# u2x.net
KiCad netlist of a schematic drawn in EAGLE
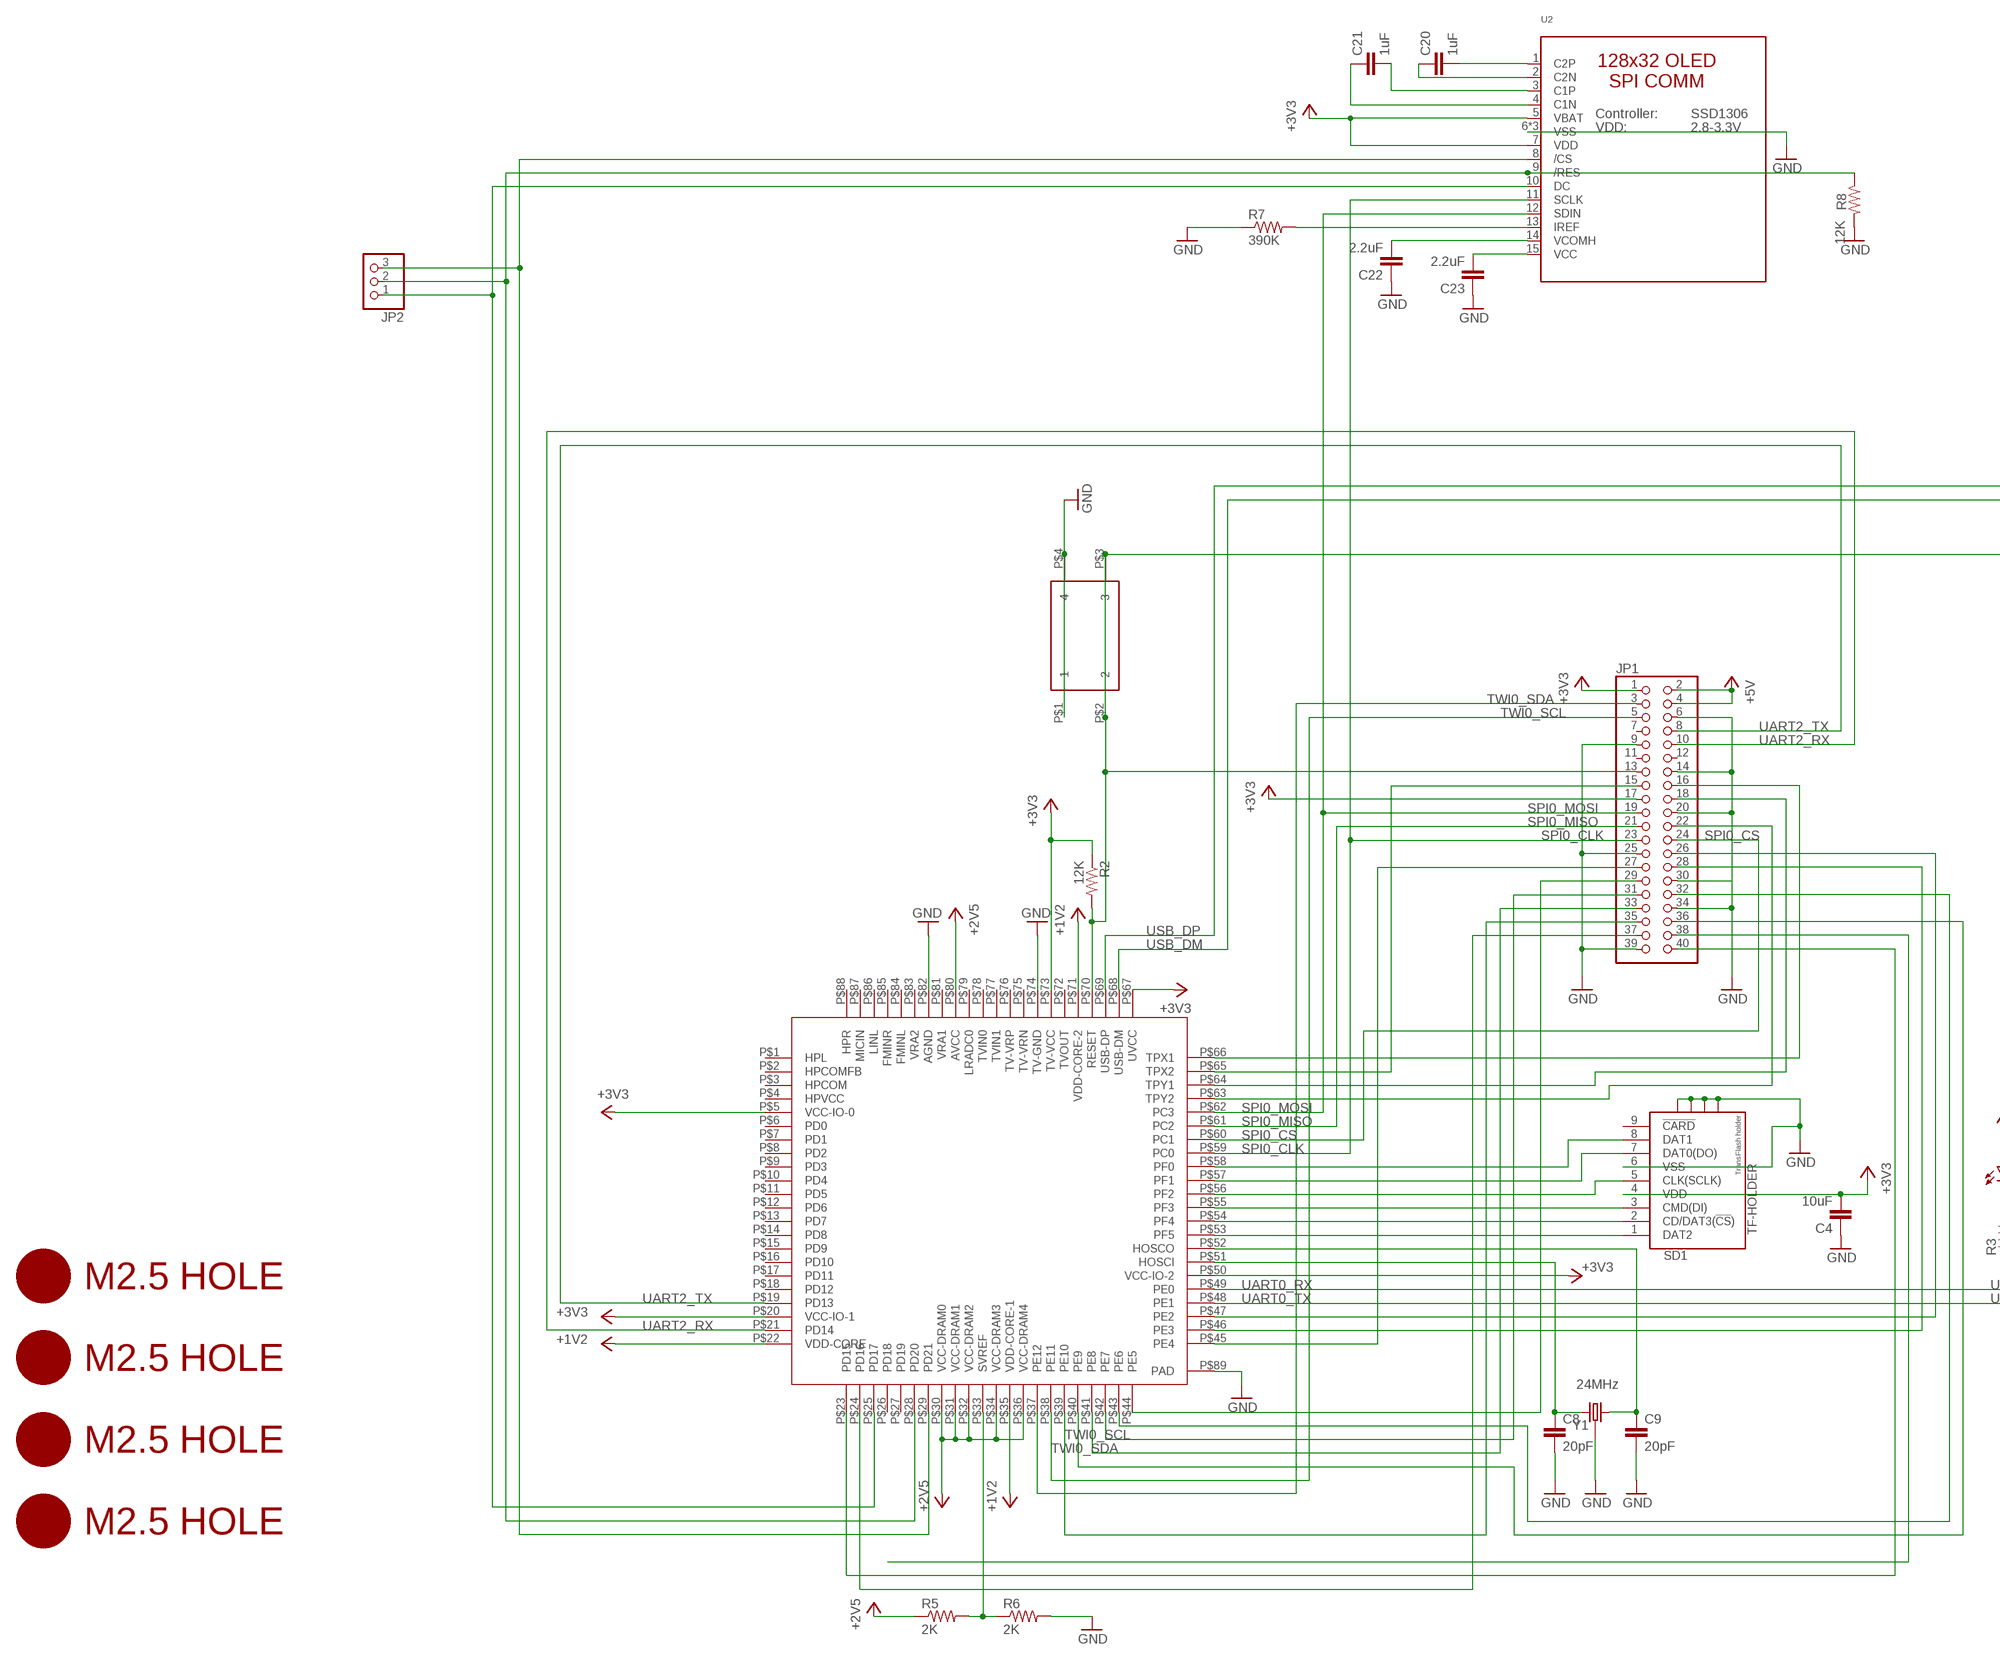
[diagram p0: schematic, sheet 1, part 1 of 2]
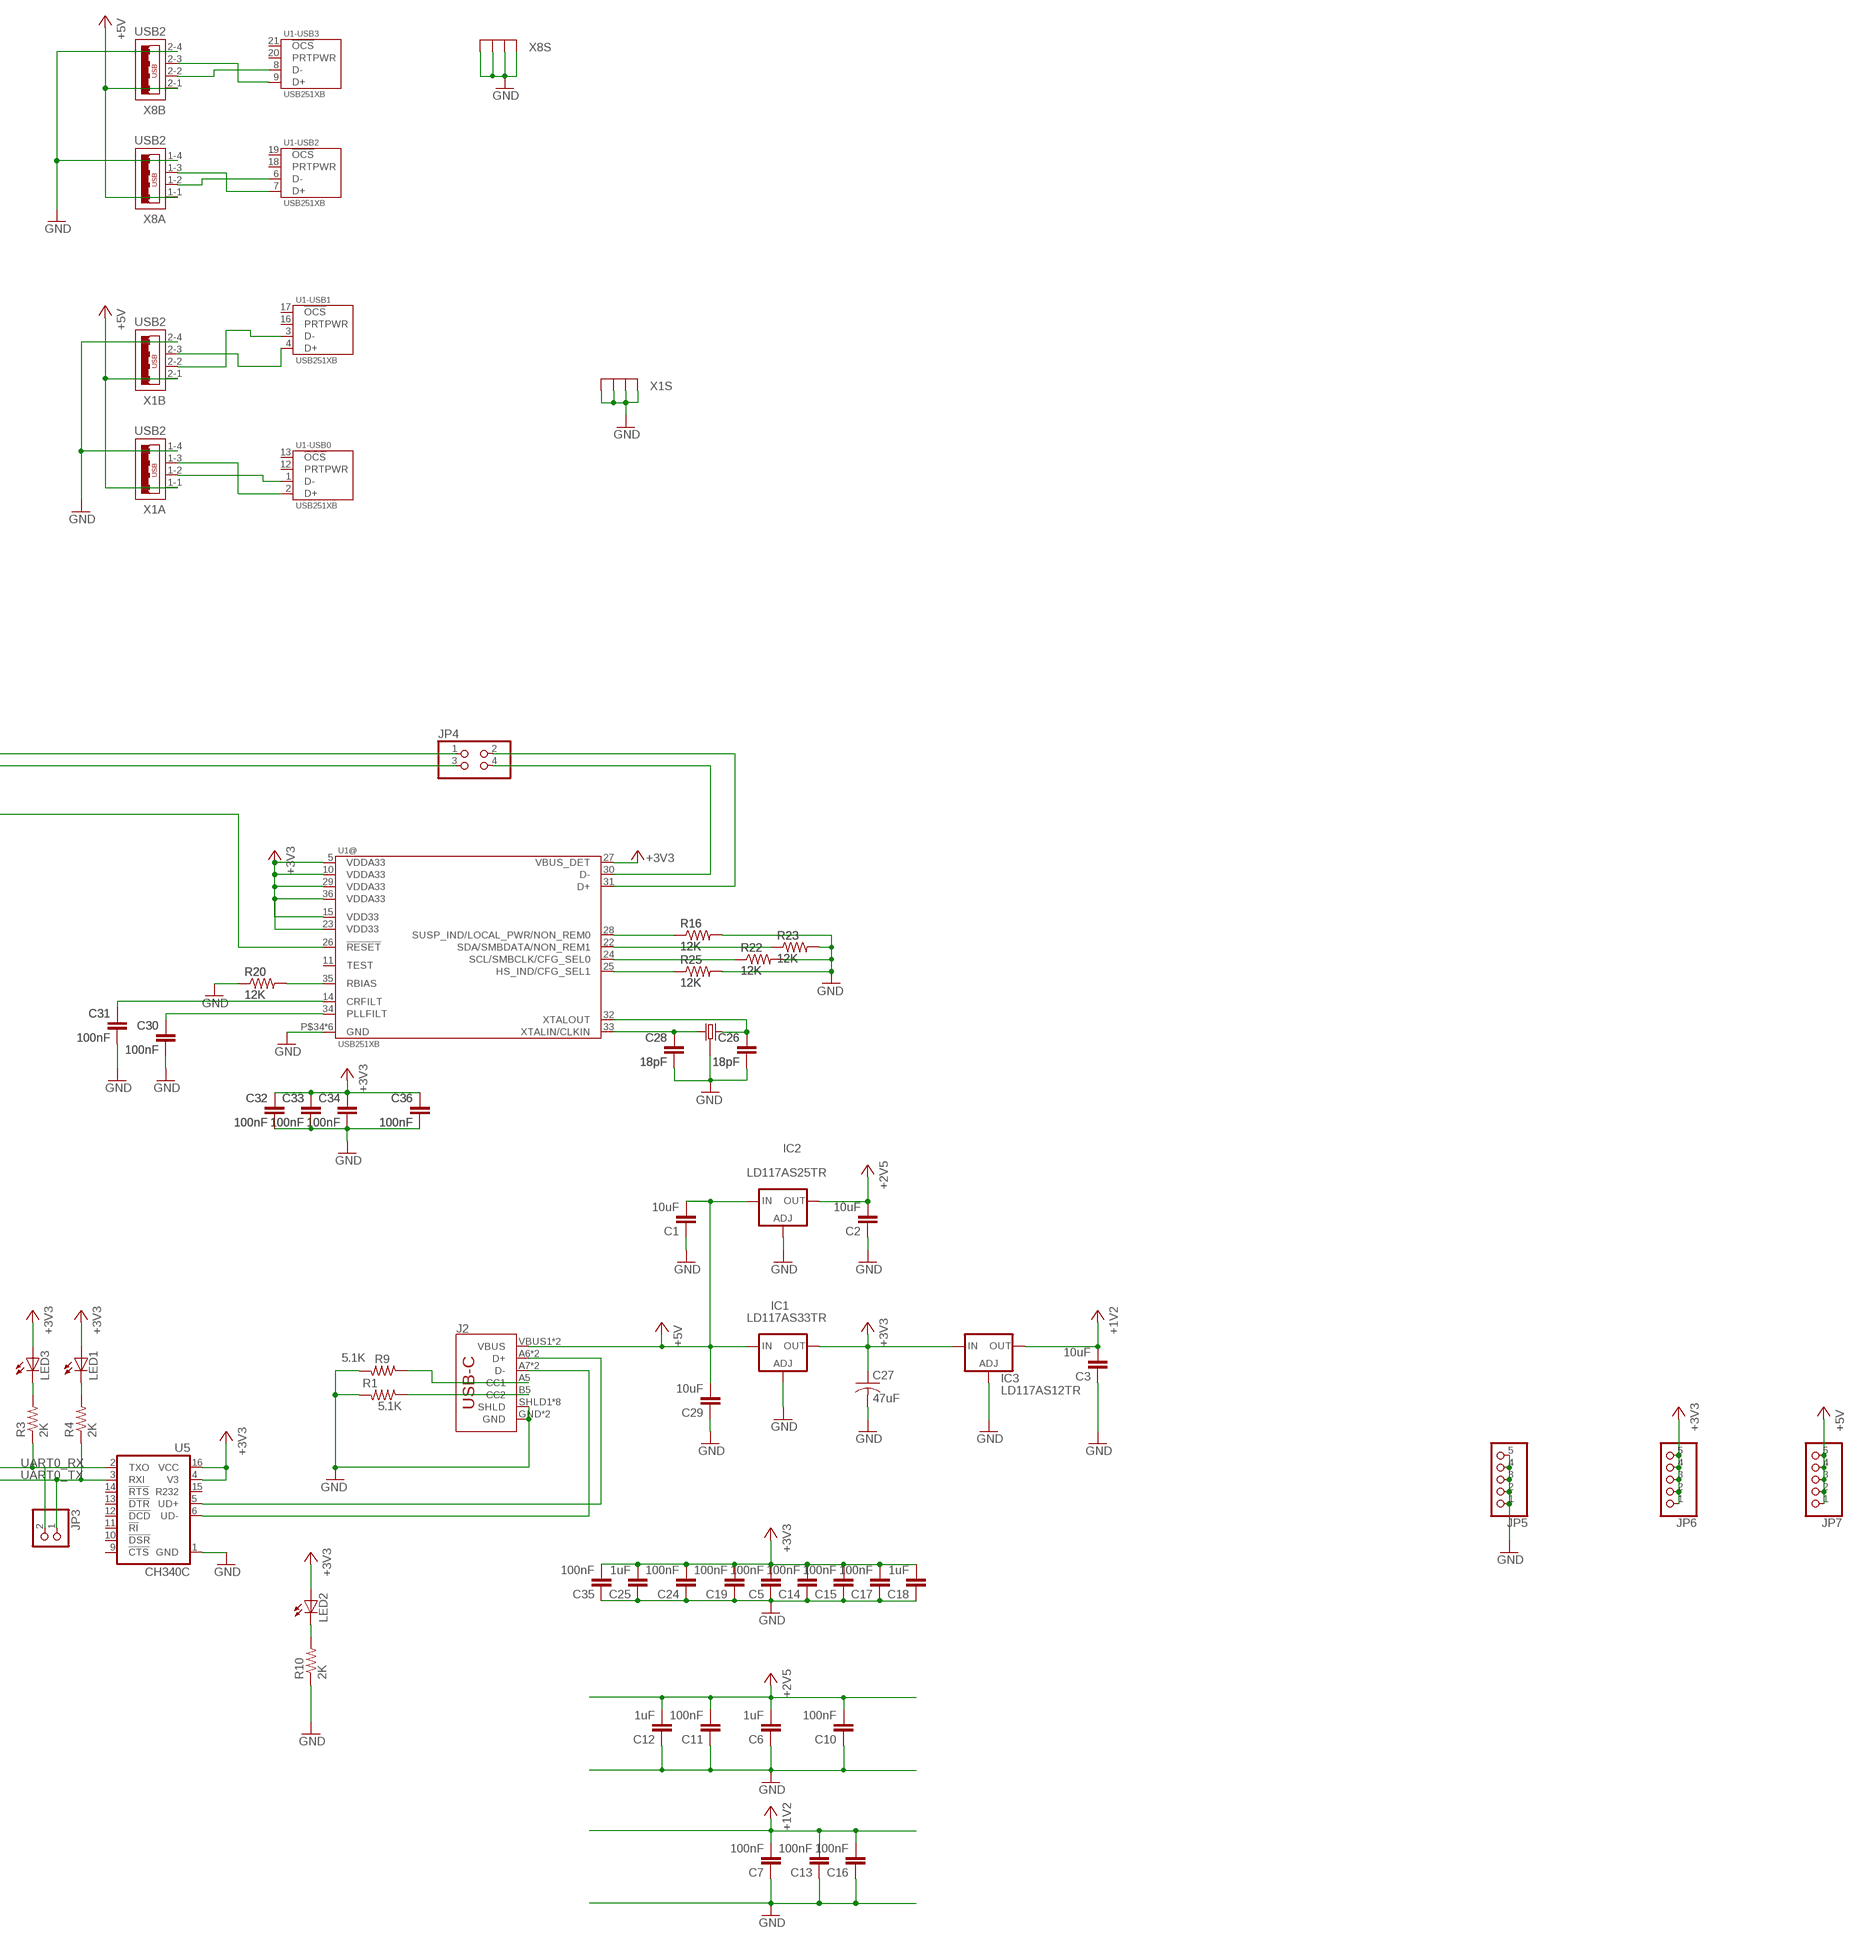
[diagram p1: schematic, sheet 1, part 2 of 2]

(export (version "E")
  (design (tool "Eeschema 10.0.6"))
  (components
    (comp (ref "C1")
      (value "10uF")
      (footprint "eagle-import:0805")
      (libsource (lib "eagle-import") (part "CAP0805"))
    )
    (comp (ref "C2")
      (value "10uF")
      (footprint "eagle-import:0805")
      (libsource (lib "eagle-import") (part "CAP0805"))
    )
    (comp (ref "C3")
      (value "10uF")
      (footprint "eagle-import:0805")
      (libsource (lib "eagle-import") (part "CAP0805"))
    )
    (comp (ref "C4")
      (value "10uF")
      (footprint "eagle-import:0805")
      (libsource (lib "eagle-import") (part "CAP0805"))
    )
    (comp (ref "C5")
      (value "100nF")
      (footprint "eagle-import:0805")
      (libsource (lib "eagle-import") (part "CAP0805"))
    )
    (comp (ref "C6")
      (value "1uF")
      (footprint "eagle-import:0805")
      (libsource (lib "eagle-import") (part "CAP0805"))
    )
    (comp (ref "C7")
      (value "100nF")
      (footprint "eagle-import:0805")
      (libsource (lib "eagle-import") (part "CAP0805"))
    )
    (comp (ref "C8")
      (value "20pF")
      (footprint "eagle-import:0805")
      (libsource (lib "eagle-import") (part "CAP0805"))
    )
    (comp (ref "C9")
      (value "20pF")
      (footprint "eagle-import:0805")
      (libsource (lib "eagle-import") (part "CAP0805"))
    )
    (comp (ref "C10")
      (value "100nF")
      (footprint "eagle-import:0805")
      (libsource (lib "eagle-import") (part "CAP0805"))
    )
    (comp (ref "C11")
      (value "100nF")
      (footprint "eagle-import:0805")
      (libsource (lib "eagle-import") (part "CAP0805"))
    )
    (comp (ref "C12")
      (value "1uF")
      (footprint "eagle-import:0805")
      (libsource (lib "eagle-import") (part "CAP0805"))
    )
    (comp (ref "C13")
      (value "100nF")
      (footprint "eagle-import:0805")
      (libsource (lib "eagle-import") (part "CAP0805"))
    )
    (comp (ref "C14")
      (value "100nF")
      (footprint "eagle-import:0805")
      (libsource (lib "eagle-import") (part "CAP0805"))
    )
    (comp (ref "C15")
      (value "100nF")
      (footprint "eagle-import:0805")
      (libsource (lib "eagle-import") (part "CAP0805"))
    )
    (comp (ref "C16")
      (value "100nF")
      (footprint "eagle-import:0805")
      (libsource (lib "eagle-import") (part "CAP0805"))
    )
    (comp (ref "C17")
      (value "100nF")
      (footprint "eagle-import:0805")
      (libsource (lib "eagle-import") (part "CAP0805"))
    )
    (comp (ref "C18")
      (value "1uF")
      (footprint "eagle-import:0805")
      (libsource (lib "eagle-import") (part "CAP0805"))
    )
    (comp (ref "C19")
      (value "100nF")
      (footprint "eagle-import:0805")
      (libsource (lib "eagle-import") (part "CAP0805"))
    )
    (comp (ref "C20")
      (value "1uF")
      (footprint "eagle-import:0805")
      (libsource (lib "eagle-import") (part "CAP0805"))
    )
    (comp (ref "C21")
      (value "1uF")
      (footprint "eagle-import:0805")
      (libsource (lib "eagle-import") (part "CAP0805"))
    )
    (comp (ref "C22")
      (value "2.2uF")
      (footprint "eagle-import:0805")
      (libsource (lib "eagle-import") (part "CAP0805"))
    )
    (comp (ref "C23")
      (value "2.2uF")
      (footprint "eagle-import:0805")
      (libsource (lib "eagle-import") (part "CAP0805"))
    )
    (comp (ref "C24")
      (value "100nF")
      (footprint "eagle-import:0805")
      (libsource (lib "eagle-import") (part "CAP0805"))
    )
    (comp (ref "C25")
      (value "1uF")
      (footprint "eagle-import:0805")
      (libsource (lib "eagle-import") (part "CAP0805"))
    )
    (comp (ref "C26")
      (value "18pF")
      (footprint "eagle-import:0805")
      (libsource (lib "eagle-import") (part "joyAnalog_CAP0805"))
    )
    (comp (ref "C27")
      (value "47uF")
      (footprint "eagle-import:C1210")
      (libsource (lib "eagle-import") (part "C-USC1210"))
    )
    (comp (ref "C28")
      (value "18pF")
      (footprint "eagle-import:0805")
      (libsource (lib "eagle-import") (part "joyAnalog_CAP0805"))
    )
    (comp (ref "C29")
      (value "10uF")
      (footprint "eagle-import:0805")
      (libsource (lib "eagle-import") (part "CAP0805"))
    )
    (comp (ref "C30")
      (value "100nF")
      (footprint "eagle-import:0805")
      (libsource (lib "eagle-import") (part "joyAnalog_CAP0805"))
    )
    (comp (ref "C31")
      (value "100nF")
      (footprint "eagle-import:0805")
      (libsource (lib "eagle-import") (part "joyAnalog_CAP0805"))
    )
    (comp (ref "C32")
      (value "100nF")
      (footprint "eagle-import:0805")
      (libsource (lib "eagle-import") (part "joyAnalog_CAP0805"))
    )
    (comp (ref "C33")
      (value "100nF")
      (footprint "eagle-import:0805")
      (libsource (lib "eagle-import") (part "joyAnalog_CAP0805"))
    )
    (comp (ref "C34")
      (value "100nF")
      (footprint "eagle-import:0805")
      (libsource (lib "eagle-import") (part "joyAnalog_CAP0805"))
    )
    (comp (ref "C35")
      (value "100nF")
      (footprint "eagle-import:0805")
      (libsource (lib "eagle-import") (part "CAP0805"))
    )
    (comp (ref "C36")
      (value "100nF")
      (footprint "eagle-import:0805")
      (libsource (lib "eagle-import") (part "joyAnalog_CAP0805"))
    )
    (comp (ref "IC1")
      (value "LD117AS33TR")
      (footprint "eagle-import:SOT223")
      (libsource (lib "eagle-import") (part "LD117A?S33TR"))
    )
    (comp (ref "IC2")
      (value "LD117AS25TR")
      (footprint "eagle-import:SOT223")
      (libsource (lib "eagle-import") (part "LD117A?S25TR"))
    )
    (comp (ref "IC3")
      (value "LD117AS12TR")
      (footprint "eagle-import:SOT223")
      (libsource (lib "eagle-import") (part "LD117A?S12TR"))
    )
    (comp (ref "J2")
      (value "USB_C16PIN")
      (footprint "eagle-import:USB-C-16P")
      (libsource (lib "eagle-import") (part "USB_C16PIN"))
    )
    (comp (ref "JP1")
      (value "PINHD-2X20-BIG")
      (footprint "eagle-import:2X20-BIG")
      (libsource (lib "eagle-import") (part "PINHD-2X20-BIG"))
    )
    (comp (ref "JP2")
      (value "PINHD-1X3CB")
      (footprint "eagle-import:1X03-CLEANBIG")
      (libsource (lib "eagle-import") (part "PINHD-1X3CB"))
    )
    (comp (ref "JP3")
      (value "PINHD-1X2")
      (footprint "eagle-import:1X02")
      (libsource (lib "eagle-import") (part "PINHD-1X2"))
    )
    (comp (ref "JP4")
      (value "PINHD-2X2")
      (footprint "eagle-import:2X02")
      (libsource (lib "eagle-import") (part "PINHD-2X2"))
    )
    (comp (ref "JP5")
      (value "PINHD-1X5")
      (footprint "eagle-import:1X05")
      (libsource (lib "eagle-import") (part "PINHD-1X5"))
    )
    (comp (ref "JP6")
      (value "PINHD-1X5")
      (footprint "eagle-import:1X05")
      (libsource (lib "eagle-import") (part "PINHD-1X5"))
    )
    (comp (ref "JP7")
      (value "PINHD-1X5")
      (footprint "eagle-import:1X05")
      (libsource (lib "eagle-import") (part "PINHD-1X5"))
    )
    (comp (ref "LED1")
      (value "LEDCHIP-LED0805")
      (footprint "eagle-import:CHIP-LED0805")
      (libsource (lib "eagle-import") (part "LEDCHIP-LED0805"))
    )
    (comp (ref "LED2")
      (value "LEDCHIP-LED0805")
      (footprint "eagle-import:CHIP-LED0805")
      (libsource (lib "eagle-import") (part "LEDCHIP-LED0805"))
    )
    (comp (ref "LED3")
      (value "LEDCHIP-LED0805")
      (footprint "eagle-import:CHIP-LED0805")
      (libsource (lib "eagle-import") (part "LEDCHIP-LED0805"))
    )
    (comp (ref "R1")
      (value "5.1K")
      (footprint "eagle-import:0805")
      (libsource (lib "eagle-import") (part "joyAnalog_RESISTOR0805-RES"))
    )
    (comp (ref "R2")
      (value "12K")
      (footprint "eagle-import:0805")
      (libsource (lib "eagle-import") (part "RESISTOR0805-RES"))
    )
    (comp (ref "R3")
      (value "2K")
      (footprint "eagle-import:0805")
      (libsource (lib "eagle-import") (part "RESISTOR0805-RES"))
    )
    (comp (ref "R4")
      (value "2K")
      (footprint "eagle-import:0805")
      (libsource (lib "eagle-import") (part "RESISTOR0805-RES"))
    )
    (comp (ref "R5")
      (value "2K")
      (footprint "eagle-import:0805")
      (libsource (lib "eagle-import") (part "RESISTOR0805-RES"))
    )
    (comp (ref "R6")
      (value "2K")
      (footprint "eagle-import:0805")
      (libsource (lib "eagle-import") (part "RESISTOR0805-RES"))
    )
    (comp (ref "R7")
      (value "390K")
      (footprint "eagle-import:0805")
      (libsource (lib "eagle-import") (part "RESISTOR0805-RES"))
    )
    (comp (ref "R8")
      (value "12K")
      (footprint "eagle-import:0805")
      (libsource (lib "eagle-import") (part "joyAnalog_RESISTOR0805-RES"))
    )
    (comp (ref "R9")
      (value "5.1K")
      (footprint "eagle-import:0805")
      (libsource (lib "eagle-import") (part "joyAnalog_RESISTOR0805-RES"))
    )
    (comp (ref "R10")
      (value "2K")
      (footprint "eagle-import:0805")
      (libsource (lib "eagle-import") (part "RESISTOR0805-RES"))
    )
    (comp (ref "R16")
      (value "12K")
      (footprint "eagle-import:0805")
      (libsource (lib "eagle-import") (part "joyAnalog_RESISTOR0805-RES"))
    )
    (comp (ref "R20")
      (value "12K")
      (footprint "eagle-import:0805")
      (libsource (lib "eagle-import") (part "joyAnalog_RESISTOR0805-RES"))
    )
    (comp (ref "R22")
      (value "12K")
      (footprint "eagle-import:0805")
      (libsource (lib "eagle-import") (part "joyAnalog_RESISTOR0805-RES"))
    )
    (comp (ref "R23")
      (value "12K")
      (footprint "eagle-import:0805")
      (libsource (lib "eagle-import") (part "joyAnalog_RESISTOR0805-RES"))
    )
    (comp (ref "R25")
      (value "12K")
      (footprint "eagle-import:0805")
      (libsource (lib "eagle-import") (part "joyAnalog_RESISTOR0805-RES"))
    )
    (comp (ref "SD1")
      (value "TF-HOLDER")
      (footprint "eagle-import:TF-PULL")
      (libsource (lib "eagle-import") (part "TF-HOLDER"))
    )
    (comp (ref "SW20")
      (value "324_SW")
      (footprint "eagle-import:342_SWICH_FOOT")
      (libsource (lib "eagle-import") (part "324_SW"))
    )
    (comp (ref "U$1")
      (value "F1C100S_DEV")
      (footprint "eagle-import:MQFN88")
      (libsource (lib "eagle-import") (part "F1C100S_DEV"))
    )
    (comp (ref "U$2")
      (value "M2.5HOLE")
      (footprint "eagle-import:M2.5HOLE")
      (libsource (lib "eagle-import") (part "M2.5HOLE"))
    )
    (comp (ref "U$3")
      (value "M2.5HOLE")
      (footprint "eagle-import:M2.5HOLE")
      (libsource (lib "eagle-import") (part "M2.5HOLE"))
    )
    (comp (ref "U$4")
      (value "M2.5HOLE")
      (footprint "eagle-import:M2.5HOLE")
      (libsource (lib "eagle-import") (part "M2.5HOLE"))
    )
    (comp (ref "U$5")
      (value "M2.5HOLE")
      (footprint "eagle-import:M2.5HOLE")
      (libsource (lib "eagle-import") (part "M2.5HOLE"))
    )
    (comp (ref "U$16")
      (value "CRYSTAL-GROUNDED")
      (footprint "eagle-import:CRYSTAL-SMD-5X3")
      (libsource (lib "eagle-import") (part "CRYSTAL-GROUNDED"))
    )
    (comp (ref "U1")
      (value "USB251XB")
      (footprint "eagle-import:QFN-36")
      (libsource (lib "eagle-import") (part "USB251XB"))
    )
    (comp (ref "U2")
      (value "LUL_DISP_OLED_UG-2864HSWEG01")
      (footprint "eagle-import:LUL_UG-2864HSWEG01_1.3_WRAPAROUND")
      (libsource (lib "eagle-import") (part "LUL_DISP_OLED_UG-2864HSWEG01"))
    )
    (comp (ref "U5")
      (value "CH340C")
      (footprint "eagle-import:SO016")
      (libsource (lib "eagle-import") (part "CH340C"))
    )
    (comp (ref "X1")
      (value "USB2")
      (footprint "eagle-import:USB2")
      (libsource (lib "eagle-import") (part "USB2"))
    )
    (comp (ref "X8")
      (value "USB2")
      (footprint "eagle-import:USB2")
      (libsource (lib "eagle-import") (part "USB2"))
    )
    (comp (ref "Y1")
      (value "24MHz")
      (footprint "eagle-import:CRYSTAL-SMD-3.2X2.5MM")
      (libsource (lib "eagle-import") (part "CRYSTAL-26MHZSMD-3.2X2.5"))
    )
  )
  (nets
    (net (code "1") (name "+1V2") (class "Default")
      (node (ref "C13") (pin "2") (pinfunction "2_2") (pintype "passive"))
      (node (ref "C16") (pin "2") (pinfunction "2_2") (pintype "passive"))
      (node (ref "C3") (pin "2") (pinfunction "2_2") (pintype "passive"))
      (node (ref "C7") (pin "2") (pinfunction "2_2") (pintype "passive"))
      (node (ref "IC3") (pin "4") (pinfunction "OUT_4") (pintype "passive"))
      (node (ref "U$1") (pin "P$22") (pinfunction "VDD-CORE_P$22") (pintype "bidirectional"))
      (node (ref "U$1") (pin "P$35") (pinfunction "VDD-CORE-1_P$35") (pintype "bidirectional"))
      (node (ref "U$1") (pin "P$71") (pinfunction "VDD-CORE-2_P$71") (pintype "bidirectional"))
    )
    (net (code "2") (name "+2V5") (class "Default")
      (node (ref "C10") (pin "2") (pinfunction "2_2") (pintype "passive"))
      (node (ref "C11") (pin "2") (pinfunction "2_2") (pintype "passive"))
      (node (ref "C12") (pin "2") (pinfunction "2_2") (pintype "passive"))
      (node (ref "C2") (pin "2") (pinfunction "2_2") (pintype "passive"))
      (node (ref "C6") (pin "2") (pinfunction "2_2") (pintype "passive"))
      (node (ref "IC2") (pin "4") (pinfunction "OUT_4") (pintype "passive"))
      (node (ref "R5") (pin "1") (pinfunction "1_1") (pintype "passive"))
      (node (ref "U$1") (pin "P$30") (pinfunction "VCC-DRAM0_P$30") (pintype "bidirectional"))
      (node (ref "U$1") (pin "P$31") (pinfunction "VCC-DRAM1_P$31") (pintype "bidirectional"))
      (node (ref "U$1") (pin "P$32") (pinfunction "VCC-DRAM2_P$32") (pintype "bidirectional"))
      (node (ref "U$1") (pin "P$34") (pinfunction "VCC-DRAM3_P$34") (pintype "bidirectional"))
      (node (ref "U$1") (pin "P$36") (pinfunction "VCC-DRAM4_P$36") (pintype "bidirectional"))
      (node (ref "U$1") (pin "P$80") (pinfunction "AVCC_P$80") (pintype "bidirectional"))
    )
    (net (code "3") (name "+3V3") (class "Default")
      (node (ref "C14") (pin "2") (pinfunction "2_2") (pintype "passive"))
      (node (ref "C15") (pin "2") (pinfunction "2_2") (pintype "passive"))
      (node (ref "C17") (pin "2") (pinfunction "2_2") (pintype "passive"))
      (node (ref "C18") (pin "2") (pinfunction "2_2") (pintype "passive"))
      (node (ref "C19") (pin "2") (pinfunction "2_2") (pintype "passive"))
      (node (ref "C24") (pin "2") (pinfunction "2_2") (pintype "passive"))
      (node (ref "C25") (pin "2") (pinfunction "2_2") (pintype "passive"))
      (node (ref "C27") (pin "1") (pinfunction "1_1") (pintype "passive"))
      (node (ref "C32") (pin "1") (pinfunction "1_1") (pintype "passive"))
      (node (ref "C33") (pin "1") (pinfunction "1_1") (pintype "passive"))
      (node (ref "C34") (pin "1") (pinfunction "1_1") (pintype "passive"))
      (node (ref "C35") (pin "2") (pinfunction "2_2") (pintype "passive"))
      (node (ref "C36") (pin "1") (pinfunction "1_1") (pintype "passive"))
      (node (ref "C4") (pin "2") (pinfunction "2_2") (pintype "passive"))
      (node (ref "C5") (pin "2") (pinfunction "2_2") (pintype "passive"))
      (node (ref "IC1") (pin "4") (pinfunction "OUT_4") (pintype "passive"))
      (node (ref "IC3") (pin "3") (pinfunction "IN_3") (pintype "input"))
      (node (ref "JP1") (pin "1") (pinfunction "1_1") (pintype "passive"))
      (node (ref "JP1") (pin "17") (pinfunction "17_17") (pintype "passive"))
      (node (ref "JP6") (pin "1") (pinfunction "1_1") (pintype "passive"))
      (node (ref "JP6") (pin "2") (pinfunction "2_2") (pintype "passive"))
      (node (ref "JP6") (pin "3") (pinfunction "3_3") (pintype "passive"))
      (node (ref "JP6") (pin "4") (pinfunction "4_4") (pintype "passive"))
      (node (ref "JP6") (pin "5") (pinfunction "5_5") (pintype "passive"))
      (node (ref "LED1") (pin "A") (pinfunction "A_A") (pintype "passive"))
      (node (ref "LED2") (pin "A") (pinfunction "A_A") (pintype "passive"))
      (node (ref "LED3") (pin "A") (pinfunction "A_A") (pintype "passive"))
      (node (ref "R2") (pin "1") (pinfunction "1_1") (pintype "passive"))
      (node (ref "SD1") (pin "4") (pinfunction "VDD_4") (pintype "power_in"))
      (node (ref "U$1") (pin "P$20") (pinfunction "VCC-IO-1_P$20") (pintype "bidirectional"))
      (node (ref "U$1") (pin "P$5") (pinfunction "VCC-IO-0_P$5") (pintype "bidirectional"))
      (node (ref "U$1") (pin "P$50") (pinfunction "VCC-IO-2_P$50") (pintype "bidirectional"))
      (node (ref "U$1") (pin "P$67") (pinfunction "UVCC_P$67") (pintype "bidirectional"))
      (node (ref "U$1") (pin "P$73") (pinfunction "TV-VCC_P$73") (pintype "bidirectional"))
      (node (ref "U1") (pin "10") (pinfunction "VDDA33_10") (pintype "bidirectional"))
      (node (ref "U1") (pin "15") (pinfunction "VDD33_15") (pintype "bidirectional"))
      (node (ref "U1") (pin "23") (pinfunction "VDD33_23") (pintype "bidirectional"))
      (node (ref "U1") (pin "27") (pinfunction "VBUS_DET_27") (pintype "bidirectional"))
      (node (ref "U1") (pin "29") (pinfunction "VDDA33_29") (pintype "bidirectional"))
      (node (ref "U1") (pin "36") (pinfunction "VDDA33_36") (pintype "bidirectional"))
      (node (ref "U1") (pin "5") (pinfunction "VDDA33_5") (pintype "bidirectional"))
      (node (ref "U2") (pin "5") (pinfunction "VBAT_5") (pintype "input"))
      (node (ref "U2") (pin "7") (pinfunction "VDD_7") (pintype "power_in"))
      (node (ref "U5") (pin "16") (pinfunction "VCC_16") (pintype "bidirectional"))
      (node (ref "U5") (pin "4") (pinfunction "V3_4") (pintype "bidirectional"))
    )
    (net (code "4") (name "+5V") (class "Default")
      (node (ref "C1") (pin "2") (pinfunction "2_2") (pintype "passive"))
      (node (ref "C29") (pin "2") (pinfunction "2_2") (pintype "passive"))
      (node (ref "IC1") (pin "3") (pinfunction "IN_3") (pintype "input"))
      (node (ref "IC2") (pin "3") (pinfunction "IN_3") (pintype "input"))
      (node (ref "J2") (pin "VBUS1") (pinfunction "VBUS_VBUS1") (pintype "bidirectional"))
      (node (ref "J2") (pin "VBUS2") (pinfunction "VBUS_VBUS2") (pintype "bidirectional"))
      (node (ref "JP1") (pin "2") (pinfunction "2_2") (pintype "passive"))
      (node (ref "JP1") (pin "4") (pinfunction "4_4") (pintype "passive"))
      (node (ref "JP7") (pin "1") (pinfunction "1_1") (pintype "passive"))
      (node (ref "JP7") (pin "2") (pinfunction "2_2") (pintype "passive"))
      (node (ref "JP7") (pin "3") (pinfunction "3_3") (pintype "passive"))
      (node (ref "JP7") (pin "4") (pinfunction "4_4") (pintype "passive"))
      (node (ref "JP7") (pin "5") (pinfunction "5_5") (pintype "passive"))
      (node (ref "X1") (pin "1-1") (pinfunction "1_1-1") (pintype "passive"))
      (node (ref "X1") (pin "2-1") (pinfunction "1_2-1") (pintype "passive"))
      (node (ref "X8") (pin "1-1") (pinfunction "1_1-1") (pintype "passive"))
      (node (ref "X8") (pin "2-1") (pinfunction "1_2-1") (pintype "passive"))
    )
    (net (code "5") (name "/SPI0_CLK") (class "Default")
      (node (ref "JP1") (pin "23") (pinfunction "23_23") (pintype "passive"))
      (node (ref "U$1") (pin "P$59") (pinfunction "PC0_P$59") (pintype "bidirectional"))
      (node (ref "U2") (pin "11") (pinfunction "SCLK_11") (pintype "bidirectional"))
    )
    (net (code "6") (name "/SPI0_CS") (class "Default")
      (node (ref "JP1") (pin "24") (pinfunction "24_24") (pintype "passive"))
      (node (ref "U$1") (pin "P$60") (pinfunction "PC1_P$60") (pintype "bidirectional"))
    )
    (net (code "7") (name "/SPI0_MISO") (class "Default")
      (node (ref "JP1") (pin "21") (pinfunction "21_21") (pintype "passive"))
      (node (ref "U$1") (pin "P$61") (pinfunction "PC2_P$61") (pintype "bidirectional"))
    )
    (net (code "8") (name "/SPI0_MOSI") (class "Default")
      (node (ref "JP1") (pin "19") (pinfunction "19_19") (pintype "passive"))
      (node (ref "U$1") (pin "P$62") (pinfunction "PC3_P$62") (pintype "bidirectional"))
      (node (ref "U2") (pin "12") (pinfunction "SDIN_12") (pintype "bidirectional"))
    )
    (net (code "9") (name "/TWI0_SCL") (class "Default")
      (node (ref "JP1") (pin "5") (pinfunction "5_5") (pintype "passive"))
      (node (ref "U$1") (pin "P$38") (pinfunction "PE11_P$38") (pintype "bidirectional"))
    )
    (net (code "10") (name "/TWI0_SDA") (class "Default")
      (node (ref "JP1") (pin "3") (pinfunction "3_3") (pintype "passive"))
      (node (ref "U$1") (pin "P$37") (pinfunction "PE12_P$37") (pintype "bidirectional"))
    )
    (net (code "11") (name "/UART0_RX") (class "Default")
      (node (ref "JP3") (pin "2") (pinfunction "2_2") (pintype "passive"))
      (node (ref "R3") (pin "1") (pinfunction "1_1") (pintype "passive"))
      (node (ref "U$1") (pin "P$49") (pinfunction "PE0_P$49") (pintype "bidirectional"))
      (node (ref "U5") (pin "2") (pinfunction "TXO_2") (pintype "bidirectional"))
    )
    (net (code "12") (name "/UART0_TX") (class "Default")
      (node (ref "JP3") (pin "1") (pinfunction "1_1") (pintype "passive"))
      (node (ref "R4") (pin "1") (pinfunction "1_1") (pintype "passive"))
      (node (ref "U$1") (pin "P$48") (pinfunction "PE1_P$48") (pintype "bidirectional"))
      (node (ref "U5") (pin "3") (pinfunction "RXI_3") (pintype "bidirectional"))
    )
    (net (code "13") (name "/UART2_RX") (class "Default")
      (node (ref "JP1") (pin "10") (pinfunction "10_10") (pintype "passive"))
      (node (ref "U$1") (pin "P$21") (pinfunction "PD14_P$21") (pintype "bidirectional"))
    )
    (net (code "14") (name "/UART2_TX") (class "Default")
      (node (ref "JP1") (pin "8") (pinfunction "8_8") (pintype "passive"))
      (node (ref "U$1") (pin "P$19") (pinfunction "PD13_P$19") (pintype "bidirectional"))
    )
    (net (code "15") (name "/USB_DM") (class "Default")
      (node (ref "JP4") (pin "3") (pinfunction "3_3") (pintype "passive"))
      (node (ref "U$1") (pin "P$68") (pinfunction "USB-DM_P$68") (pintype "bidirectional"))
    )
    (net (code "16") (name "/USB_DP") (class "Default")
      (node (ref "JP4") (pin "1") (pinfunction "1_1") (pintype "passive"))
      (node (ref "U$1") (pin "P$69") (pinfunction "USB-DP_P$69") (pintype "bidirectional"))
    )
    (net (code "17") (name "GND") (class "Default")
      (node (ref "C1") (pin "1") (pinfunction "1_1") (pintype "passive"))
      (node (ref "C10") (pin "1") (pinfunction "1_1") (pintype "passive"))
      (node (ref "C11") (pin "1") (pinfunction "1_1") (pintype "passive"))
      (node (ref "C12") (pin "1") (pinfunction "1_1") (pintype "passive"))
      (node (ref "C13") (pin "1") (pinfunction "1_1") (pintype "passive"))
      (node (ref "C14") (pin "1") (pinfunction "1_1") (pintype "passive"))
      (node (ref "C15") (pin "1") (pinfunction "1_1") (pintype "passive"))
      (node (ref "C16") (pin "1") (pinfunction "1_1") (pintype "passive"))
      (node (ref "C17") (pin "1") (pinfunction "1_1") (pintype "passive"))
      (node (ref "C18") (pin "1") (pinfunction "1_1") (pintype "passive"))
      (node (ref "C19") (pin "1") (pinfunction "1_1") (pintype "passive"))
      (node (ref "C2") (pin "1") (pinfunction "1_1") (pintype "passive"))
      (node (ref "C22") (pin "1") (pinfunction "1_1") (pintype "passive"))
      (node (ref "C23") (pin "1") (pinfunction "1_1") (pintype "passive"))
      (node (ref "C24") (pin "1") (pinfunction "1_1") (pintype "passive"))
      (node (ref "C25") (pin "1") (pinfunction "1_1") (pintype "passive"))
      (node (ref "C26") (pin "2") (pinfunction "2_2") (pintype "passive"))
      (node (ref "C27") (pin "2") (pinfunction "2_2") (pintype "passive"))
      (node (ref "C28") (pin "2") (pinfunction "2_2") (pintype "passive"))
      (node (ref "C29") (pin "1") (pinfunction "1_1") (pintype "passive"))
      (node (ref "C3") (pin "1") (pinfunction "1_1") (pintype "passive"))
      (node (ref "C30") (pin "2") (pinfunction "2_2") (pintype "passive"))
      (node (ref "C31") (pin "2") (pinfunction "2_2") (pintype "passive"))
      (node (ref "C32") (pin "2") (pinfunction "2_2") (pintype "passive"))
      (node (ref "C33") (pin "2") (pinfunction "2_2") (pintype "passive"))
      (node (ref "C34") (pin "2") (pinfunction "2_2") (pintype "passive"))
      (node (ref "C35") (pin "1") (pinfunction "1_1") (pintype "passive"))
      (node (ref "C36") (pin "2") (pinfunction "2_2") (pintype "passive"))
      (node (ref "C4") (pin "1") (pinfunction "1_1") (pintype "passive"))
      (node (ref "C5") (pin "1") (pinfunction "1_1") (pintype "passive"))
      (node (ref "C6") (pin "1") (pinfunction "1_1") (pintype "passive"))
      (node (ref "C7") (pin "1") (pinfunction "1_1") (pintype "passive"))
      (node (ref "C8") (pin "2") (pinfunction "2_2") (pintype "passive"))
      (node (ref "C9") (pin "2") (pinfunction "2_2") (pintype "passive"))
      (node (ref "IC1") (pin "1") (pinfunction "ADJ_1") (pintype "input"))
      (node (ref "IC2") (pin "1") (pinfunction "ADJ_1") (pintype "input"))
      (node (ref "IC3") (pin "1") (pinfunction "ADJ_1") (pintype "input"))
      (node (ref "J2") (pin "GND") (pinfunction "GND_GND") (pintype "bidirectional"))
      (node (ref "J2") (pin "GND2") (pinfunction "GND_GND2") (pintype "bidirectional"))
      (node (ref "J2") (pin "SHLD1") (pinfunction "SHLD_SHLD1") (pintype "bidirectional"))
      (node (ref "J2") (pin "SHLD2") (pinfunction "SHLD_SHLD2") (pintype "bidirectional"))
      (node (ref "J2") (pin "SHLD3") (pinfunction "SHLD_SHLD3") (pintype "bidirectional"))
      (node (ref "J2") (pin "SHLD4") (pinfunction "SHLD_SHLD4") (pintype "bidirectional"))
      (node (ref "J2") (pin "SHLD5") (pinfunction "SHLD_SHLD5") (pintype "bidirectional"))
      (node (ref "J2") (pin "SHLD6") (pinfunction "SHLD_SHLD6") (pintype "bidirectional"))
      (node (ref "J2") (pin "SHLD7") (pinfunction "SHLD_SHLD7") (pintype "bidirectional"))
      (node (ref "J2") (pin "SHLD8") (pinfunction "SHLD_SHLD8") (pintype "bidirectional"))
      (node (ref "JP1") (pin "14") (pinfunction "14_14") (pintype "passive"))
      (node (ref "JP1") (pin "20") (pinfunction "20_20") (pintype "passive"))
      (node (ref "JP1") (pin "25") (pinfunction "25_25") (pintype "passive"))
      (node (ref "JP1") (pin "30") (pinfunction "30_30") (pintype "passive"))
      (node (ref "JP1") (pin "34") (pinfunction "34_34") (pintype "passive"))
      (node (ref "JP1") (pin "39") (pinfunction "39_39") (pintype "passive"))
      (node (ref "JP1") (pin "6") (pinfunction "6_6") (pintype "passive"))
      (node (ref "JP1") (pin "9") (pinfunction "9_9") (pintype "passive"))
      (node (ref "JP5") (pin "1") (pinfunction "1_1") (pintype "passive"))
      (node (ref "JP5") (pin "2") (pinfunction "2_2") (pintype "passive"))
      (node (ref "JP5") (pin "3") (pinfunction "3_3") (pintype "passive"))
      (node (ref "JP5") (pin "4") (pinfunction "4_4") (pintype "passive"))
      (node (ref "JP5") (pin "5") (pinfunction "5_5") (pintype "passive"))
      (node (ref "R1") (pin "2") (pinfunction "2_2") (pintype "passive"))
      (node (ref "R10") (pin "1") (pinfunction "1_1") (pintype "passive"))
      (node (ref "R16") (pin "2") (pinfunction "2_2") (pintype "passive"))
      (node (ref "R20") (pin "1") (pinfunction "1_1") (pintype "passive"))
      (node (ref "R22") (pin "2") (pinfunction "2_2") (pintype "passive"))
      (node (ref "R23") (pin "2") (pinfunction "2_2") (pintype "passive"))
      (node (ref "R25") (pin "2") (pinfunction "2_2") (pintype "passive"))
      (node (ref "R6") (pin "2") (pinfunction "2_2") (pintype "passive"))
      (node (ref "R7") (pin "1") (pinfunction "1_1") (pintype "passive"))
      (node (ref "R8") (pin "2") (pinfunction "2_2") (pintype "passive"))
      (node (ref "R9") (pin "2") (pinfunction "2_2") (pintype "passive"))
      (node (ref "SD1") (pin "6") (pinfunction "VSS_6") (pintype "power_in"))
      (node (ref "SD1") (pin "S1") (pinfunction "S1_S1") (pintype "passive"))
      (node (ref "SD1") (pin "S2") (pinfunction "S2_S2") (pintype "passive"))
      (node (ref "SD1") (pin "S3") (pinfunction "S3_S3") (pintype "passive"))
      (node (ref "SD1") (pin "S4") (pinfunction "S4_S4") (pintype "passive"))
      (node (ref "SW20") (pin "P$1") (pinfunction "1_P$1") (pintype "bidirectional"))
      (node (ref "SW20") (pin "P$4") (pinfunction "4_P$4") (pintype "bidirectional"))
      (node (ref "U$1") (pin "P$74") (pinfunction "TV-GND_P$74") (pintype "bidirectional"))
      (node (ref "U$1") (pin "P$82") (pinfunction "AGND_P$82") (pintype "bidirectional"))
      (node (ref "U$1") (pin "P$89") (pinfunction "PAD_P$89") (pintype "bidirectional"))
      (node (ref "U$16") (pin "2") (pinfunction "3_2") (pintype "passive"))
      (node (ref "U$16") (pin "4") (pinfunction "3_4") (pintype "passive"))
      (node (ref "U1") (pin "P$34") (pinfunction "GND_P$34") (pintype "bidirectional"))
      (node (ref "U1") (pin "P$35") (pinfunction "GND_P$35") (pintype "bidirectional"))
      (node (ref "U1") (pin "P$36") (pinfunction "GND_P$36") (pintype "bidirectional"))
      (node (ref "U1") (pin "P$37") (pinfunction "GND_P$37") (pintype "bidirectional"))
      (node (ref "U1") (pin "P$38") (pinfunction "GND_P$38") (pintype "bidirectional"))
      (node (ref "U1") (pin "PAD") (pinfunction "GND_PAD") (pintype "bidirectional"))
      (node (ref "U2") (pin "16") (pinfunction "VSS_16") (pintype "power_in"))
      (node (ref "U2") (pin "17") (pinfunction "VSS_17") (pintype "power_in"))
      (node (ref "U2") (pin "6") (pinfunction "VSS_6") (pintype "power_in"))
      (node (ref "U5") (pin "1") (pinfunction "GND_1") (pintype "bidirectional"))
      (node (ref "X1") (pin "1-4") (pinfunction "4_1-4") (pintype "passive"))
      (node (ref "X1") (pin "2-4") (pinfunction "4_2-4") (pintype "passive"))
      (node (ref "X1") (pin "M1") (pinfunction "S1_M1") (pintype "passive"))
      (node (ref "X1") (pin "M2") (pinfunction "S2_M2") (pintype "passive"))
      (node (ref "X1") (pin "M3") (pinfunction "S3_M3") (pintype "passive"))
      (node (ref "X1") (pin "M4") (pinfunction "S4_M4") (pintype "passive"))
      (node (ref "X8") (pin "1-4") (pinfunction "4_1-4") (pintype "passive"))
      (node (ref "X8") (pin "2-4") (pinfunction "4_2-4") (pintype "passive"))
      (node (ref "X8") (pin "M1") (pinfunction "S1_M1") (pintype "passive"))
      (node (ref "X8") (pin "M2") (pinfunction "S2_M2") (pintype "passive"))
      (node (ref "X8") (pin "M3") (pinfunction "S3_M3") (pintype "passive"))
      (node (ref "X8") (pin "M4") (pinfunction "S4_M4") (pintype "passive"))
      (node (ref "Y1") (pin "2") (pinfunction "3_2") (pintype "passive"))
      (node (ref "Y1") (pin "4") (pinfunction "3_4") (pintype "passive"))
    )
    (net (code "18") (name "Net-(J2-CC1)") (class "Default")
      (node (ref "J2") (pin "A5") (pinfunction "CC1_A5") (pintype "bidirectional"))
      (node (ref "R9") (pin "1") (pinfunction "1_1") (pintype "passive"))
    )
    (net (code "19") (name "Net-(J2-CC2)") (class "Default")
      (node (ref "J2") (pin "B5") (pinfunction "CC2_B5") (pintype "bidirectional"))
      (node (ref "R1") (pin "1") (pinfunction "1_1") (pintype "passive"))
    )
    (net (code "20") (name "Net-(LED1-PadC)") (class "Default")
      (node (ref "LED1") (pin "C") (pinfunction "C_C") (pintype "passive"))
      (node (ref "R4") (pin "2") (pinfunction "2_2") (pintype "passive"))
    )
    (net (code "21") (name "Net-(LED2-PadC)") (class "Default")
      (node (ref "LED2") (pin "C") (pinfunction "C_C") (pintype "passive"))
      (node (ref "R10") (pin "2") (pinfunction "2_2") (pintype "passive"))
    )
    (net (code "22") (name "Net-(LED3-PadC)") (class "Default")
      (node (ref "LED3") (pin "C") (pinfunction "C_C") (pintype "passive"))
      (node (ref "R3") (pin "2") (pinfunction "2_2") (pintype "passive"))
    )
    (net (code "23") (name "Net-(SD1-CD{slash}DAT3(~{CS}))") (class "Default")
      (node (ref "SD1") (pin "2") (pinfunction "CD/DAT3(~{CS})_2") (pintype "bidirectional"))
      (node (ref "U$1") (pin "P$54") (pinfunction "PF4_P$54") (pintype "bidirectional"))
    )
    (net (code "24") (name "Net-(SD1-CLK(SCLK))") (class "Default")
      (node (ref "SD1") (pin "5") (pinfunction "CLK(SCLK)_5") (pintype "input"))
      (node (ref "U$1") (pin "P$56") (pinfunction "PF2_P$56") (pintype "bidirectional"))
    )
    (net (code "25") (name "Net-(SD1-CMD(DI))") (class "Default")
      (node (ref "SD1") (pin "3") (pinfunction "CMD(DI)_3") (pintype "bidirectional"))
      (node (ref "U$1") (pin "P$55") (pinfunction "PF3_P$55") (pintype "bidirectional"))
    )
    (net (code "26") (name "Net-(SD1-DAT0(DO))") (class "Default")
      (node (ref "SD1") (pin "7") (pinfunction "DAT0(DO)_7") (pintype "bidirectional"))
      (node (ref "U$1") (pin "P$57") (pinfunction "PF1_P$57") (pintype "bidirectional"))
    )
    (net (code "27") (name "Net-(SD1-DAT1)") (class "Default")
      (node (ref "SD1") (pin "8") (pinfunction "DAT1_8") (pintype "bidirectional"))
      (node (ref "U$1") (pin "P$58") (pinfunction "PF0_P$58") (pintype "bidirectional"))
    )
    (net (code "28") (name "Net-(SD1-DAT2)") (class "Default")
      (node (ref "SD1") (pin "1") (pinfunction "DAT2_1") (pintype "bidirectional"))
      (node (ref "U$1") (pin "P$53") (pinfunction "PF5_P$53") (pintype "bidirectional"))
    )
    (net (code "29") (name "Net-(SW20-2)") (class "Default")
      (node (ref "JP1") (pin "13") (pinfunction "13_13") (pintype "passive"))
      (node (ref "R2") (pin "2") (pinfunction "2_2") (pintype "passive"))
      (node (ref "SW20") (pin "P$2") (pinfunction "2_P$2") (pintype "bidirectional"))
      (node (ref "SW20") (pin "P$3") (pinfunction "3_P$3") (pintype "bidirectional"))
      (node (ref "U$1") (pin "P$70") (pinfunction "RESET_P$70") (pintype "bidirectional"))
      (node (ref "U1") (pin "26") (pinfunction "~{RESET}_26") (pintype "bidirectional"))
    )
    (net (code "30") (name "Net-(U$1-HOSCI)") (class "Default")
      (node (ref "C8") (pin "1") (pinfunction "1_1") (pintype "passive"))
      (node (ref "U$1") (pin "P$51") (pinfunction "HOSCI_P$51") (pintype "bidirectional"))
      (node (ref "Y1") (pin "1") (pinfunction "1_1") (pintype "passive"))
    )
    (net (code "31") (name "Net-(U$1-HOSCO)") (class "Default")
      (node (ref "C9") (pin "1") (pinfunction "1_1") (pintype "passive"))
      (node (ref "U$1") (pin "P$52") (pinfunction "HOSCO_P$52") (pintype "bidirectional"))
      (node (ref "Y1") (pin "3") (pinfunction "2_3") (pintype "passive"))
    )
    (net (code "32") (name "Net-(U$1-PD15)") (class "Default")
      (node (ref "JP1") (pin "40") (pinfunction "40_40") (pintype "passive"))
      (node (ref "U$1") (pin "P$23") (pinfunction "PD15_P$23") (pintype "bidirectional"))
    )
    (net (code "33") (name "Net-(U$1-PD16)") (class "Default")
      (node (ref "JP1") (pin "37") (pinfunction "37_37") (pintype "passive"))
      (node (ref "U$1") (pin "P$24") (pinfunction "PD16_P$24") (pintype "bidirectional"))
    )
    (net (code "34") (name "Net-(U$1-PD17)") (class "Default")
      (node (ref "JP2") (pin "1") (pinfunction "1_1") (pintype "passive"))
      (node (ref "U$1") (pin "P$25") (pinfunction "PD17_P$25") (pintype "bidirectional"))
      (node (ref "U2") (pin "10") (pinfunction "DC_10") (pintype "input"))
    )
    (net (code "35") (name "Net-(U$1-PD20)") (class "Default")
      (node (ref "JP2") (pin "2") (pinfunction "2_2") (pintype "passive"))
      (node (ref "R8") (pin "1") (pinfunction "1_1") (pintype "passive"))
      (node (ref "U$1") (pin "P$28") (pinfunction "PD20_P$28") (pintype "bidirectional"))
      (node (ref "U2") (pin "9") (pinfunction "/RES_9") (pintype "input"))
    )
    (net (code "36") (name "Net-(U$1-PD21)") (class "Default")
      (node (ref "JP2") (pin "3") (pinfunction "3_3") (pintype "passive"))
      (node (ref "U$1") (pin "P$29") (pinfunction "PD21_P$29") (pintype "bidirectional"))
      (node (ref "U2") (pin "8") (pinfunction "/CS_8") (pintype "input"))
    )
    (net (code "37") (name "Net-(U$1-PE2)") (class "Default")
      (node (ref "JP1") (pin "26") (pinfunction "26_26") (pintype "passive"))
      (node (ref "U$1") (pin "P$47") (pinfunction "PE2_P$47") (pintype "bidirectional"))
    )
    (net (code "38") (name "Net-(U$1-PE3)") (class "Default")
      (node (ref "JP1") (pin "28") (pinfunction "28_28") (pintype "passive"))
      (node (ref "U$1") (pin "P$46") (pinfunction "PE3_P$46") (pintype "bidirectional"))
    )
    (net (code "39") (name "Net-(U$1-PE4)") (class "Default")
      (node (ref "JP1") (pin "27") (pinfunction "27_27") (pintype "passive"))
      (node (ref "U$1") (pin "P$45") (pinfunction "PE4_P$45") (pintype "bidirectional"))
    )
    (net (code "40") (name "Net-(U$1-PE5)") (class "Default")
      (node (ref "JP1") (pin "29") (pinfunction "29_29") (pintype "passive"))
      (node (ref "U$1") (pin "P$44") (pinfunction "PE5_P$44") (pintype "bidirectional"))
    )
    (net (code "41") (name "Net-(U$1-PE6)") (class "Default")
      (node (ref "JP1") (pin "32") (pinfunction "32_32") (pintype "passive"))
      (node (ref "U$1") (pin "P$43") (pinfunction "PE6_P$43") (pintype "bidirectional"))
    )
    (net (code "42") (name "Net-(U$1-PE7)") (class "Default")
      (node (ref "JP1") (pin "31") (pinfunction "31_31") (pintype "passive"))
      (node (ref "U$1") (pin "P$42") (pinfunction "PE7_P$42") (pintype "bidirectional"))
    )
    (net (code "43") (name "Net-(U$1-PE8)") (class "Default")
      (node (ref "JP1") (pin "33") (pinfunction "33_33") (pintype "passive"))
      (node (ref "U$1") (pin "P$41") (pinfunction "PE8_P$41") (pintype "bidirectional"))
    )
    (net (code "44") (name "Net-(U$1-PE9)") (class "Default")
      (node (ref "JP1") (pin "36") (pinfunction "36_36") (pintype "passive"))
      (node (ref "U$1") (pin "P$40") (pinfunction "PE9_P$40") (pintype "bidirectional"))
    )
    (net (code "45") (name "Net-(U$1-PE10)") (class "Default")
      (node (ref "JP1") (pin "35") (pinfunction "35_35") (pintype "passive"))
      (node (ref "U$1") (pin "P$39") (pinfunction "PE10_P$39") (pintype "bidirectional"))
    )
    (net (code "46") (name "Net-(U$1-SVREF)") (class "Default")
      (node (ref "R5") (pin "2") (pinfunction "2_2") (pintype "passive"))
      (node (ref "R6") (pin "1") (pinfunction "1_1") (pintype "passive"))
      (node (ref "U$1") (pin "P$33") (pinfunction "SVREF_P$33") (pintype "bidirectional"))
    )
    (net (code "47") (name "Net-(U$1-TPX1)") (class "Default")
      (node (ref "JP1") (pin "16") (pinfunction "16_16") (pintype "passive"))
      (node (ref "U$1") (pin "P$66") (pinfunction "TPX1_P$66") (pintype "bidirectional"))
    )
    (net (code "48") (name "Net-(U$1-TPX2)") (class "Default")
      (node (ref "JP1") (pin "15") (pinfunction "15_15") (pintype "passive"))
      (node (ref "U$1") (pin "P$65") (pinfunction "TPX2_P$65") (pintype "bidirectional"))
    )
    (net (code "49") (name "Net-(U$1-TPY1)") (class "Default")
      (node (ref "JP1") (pin "18") (pinfunction "18_18") (pintype "passive"))
      (node (ref "U$1") (pin "P$64") (pinfunction "TPY1_P$64") (pintype "bidirectional"))
    )
    (net (code "50") (name "Net-(U$1-TPY2)") (class "Default")
      (node (ref "JP1") (pin "22") (pinfunction "22_22") (pintype "passive"))
      (node (ref "U$1") (pin "P$63") (pinfunction "TPY2_P$63") (pintype "bidirectional"))
    )
    (net (code "51") (name "Net-(U$16-1)") (class "Default")
      (node (ref "C26") (pin "1") (pinfunction "1_1") (pintype "passive"))
      (node (ref "U$16") (pin "3") (pinfunction "1_3") (pintype "passive"))
      (node (ref "U1") (pin "32") (pinfunction "XTALOUT_32") (pintype "bidirectional"))
    )
    (net (code "52") (name "Net-(U$16-2)") (class "Default")
      (node (ref "C28") (pin "1") (pinfunction "1_1") (pintype "passive"))
      (node (ref "U$16") (pin "1") (pinfunction "2_1") (pintype "passive"))
      (node (ref "U1") (pin "33") (pinfunction "XTALIN/CLKIN_33") (pintype "bidirectional"))
    )
    (net (code "53") (name "Net-(U1A-D+)") (class "Default")
      (node (ref "U1") (pin "2") (pinfunction "D+_2") (pintype "bidirectional"))
      (node (ref "X1") (pin "1-3") (pinfunction "3_1-3") (pintype "passive"))
    )
    (net (code "54") (name "Net-(U1A-D-)") (class "Default")
      (node (ref "U1") (pin "1") (pinfunction "D-_1") (pintype "bidirectional"))
      (node (ref "X1") (pin "1-2") (pinfunction "2_1-2") (pintype "passive"))
    )
    (net (code "55") (name "Net-(U1B-D+)") (class "Default")
      (node (ref "U1") (pin "4") (pinfunction "D+_4") (pintype "bidirectional"))
      (node (ref "X1") (pin "2-3") (pinfunction "3_2-3") (pintype "passive"))
    )
    (net (code "56") (name "Net-(U1B-D-)") (class "Default")
      (node (ref "U1") (pin "3") (pinfunction "D-_3") (pintype "bidirectional"))
      (node (ref "X1") (pin "2-2") (pinfunction "2_2-2") (pintype "passive"))
    )
    (net (code "57") (name "Net-(U1C-D+)") (class "Default")
      (node (ref "U1") (pin "7") (pinfunction "D+_7") (pintype "bidirectional"))
      (node (ref "X8") (pin "1-3") (pinfunction "3_1-3") (pintype "passive"))
    )
    (net (code "58") (name "Net-(U1C-D-)") (class "Default")
      (node (ref "U1") (pin "6") (pinfunction "D-_6") (pintype "bidirectional"))
      (node (ref "X8") (pin "1-2") (pinfunction "2_1-2") (pintype "passive"))
    )
    (net (code "59") (name "Net-(U1D-D+)") (class "Default")
      (node (ref "U1") (pin "9") (pinfunction "D+_9") (pintype "bidirectional"))
      (node (ref "X8") (pin "2-3") (pinfunction "3_2-3") (pintype "passive"))
    )
    (net (code "60") (name "Net-(U1D-D-)") (class "Default")
      (node (ref "U1") (pin "8") (pinfunction "D-_8") (pintype "bidirectional"))
      (node (ref "X8") (pin "2-2") (pinfunction "2_2-2") (pintype "passive"))
    )
    (net (code "61") (name "Net-(U1E-CRFILT)") (class "Default")
      (node (ref "C31") (pin "1") (pinfunction "1_1") (pintype "passive"))
      (node (ref "U1") (pin "14") (pinfunction "CRFILT_14") (pintype "bidirectional"))
    )
    (net (code "62") (name "Net-(U1E-D+)") (class "Default")
      (node (ref "JP4") (pin "2") (pinfunction "2_2") (pintype "passive"))
      (node (ref "U1") (pin "31") (pinfunction "D+_31") (pintype "bidirectional"))
    )
    (net (code "63") (name "Net-(U1E-D-)") (class "Default")
      (node (ref "JP4") (pin "4") (pinfunction "4_4") (pintype "passive"))
      (node (ref "U1") (pin "30") (pinfunction "D-_30") (pintype "bidirectional"))
    )
    (net (code "64") (name "Net-(U1E-HS_IND{slash}CFG_SEL1)") (class "Default")
      (node (ref "R25") (pin "1") (pinfunction "1_1") (pintype "passive"))
      (node (ref "U1") (pin "25") (pinfunction "HS_IND/CFG_SEL1_25") (pintype "bidirectional"))
    )
    (net (code "65") (name "Net-(U1E-PLLFILT)") (class "Default")
      (node (ref "C30") (pin "1") (pinfunction "1_1") (pintype "passive"))
      (node (ref "U1") (pin "34") (pinfunction "PLLFILT_34") (pintype "bidirectional"))
    )
    (net (code "66") (name "Net-(U1E-RBIAS)") (class "Default")
      (node (ref "R20") (pin "2") (pinfunction "2_2") (pintype "passive"))
      (node (ref "U1") (pin "35") (pinfunction "RBIAS_35") (pintype "bidirectional"))
    )
    (net (code "67") (name "Net-(U1E-SCL{slash}SMBCLK{slash}CFG_SEL0)") (class "Default")
      (node (ref "R22") (pin "1") (pinfunction "1_1") (pintype "passive"))
      (node (ref "U1") (pin "24") (pinfunction "SCL/SMBCLK/CFG_SEL0_24") (pintype "bidirectional"))
    )
    (net (code "68") (name "Net-(U1E-SDA{slash}SMBDATA{slash}NON_REM1)") (class "Default")
      (node (ref "R23") (pin "1") (pinfunction "1_1") (pintype "passive"))
      (node (ref "U1") (pin "22") (pinfunction "SDA/SMBDATA/NON_REM1_22") (pintype "bidirectional"))
    )
    (net (code "69") (name "Net-(U1E-SUSP_IND{slash}LOCAL_PWR{slash}NON_REM0)") (class "Default")
      (node (ref "R16") (pin "1") (pinfunction "1_1") (pintype "passive"))
      (node (ref "U1") (pin "28") (pinfunction "SUSP_IND/LOCAL_PWR/NON_REM0_28") (pintype "bidirectional"))
    )
    (net (code "70") (name "Net-(U2-C1N)") (class "Default")
      (node (ref "C21") (pin "1") (pinfunction "1_1") (pintype "passive"))
      (node (ref "U2") (pin "4") (pinfunction "C1N_4") (pintype "input"))
    )
    (net (code "71") (name "Net-(U2-C1P)") (class "Default")
      (node (ref "C21") (pin "2") (pinfunction "2_2") (pintype "passive"))
      (node (ref "U2") (pin "3") (pinfunction "C1P_3") (pintype "input"))
    )
    (net (code "72") (name "Net-(U2-C2N)") (class "Default")
      (node (ref "C20") (pin "1") (pinfunction "1_1") (pintype "passive"))
      (node (ref "U2") (pin "2") (pinfunction "C2N_2") (pintype "input"))
    )
    (net (code "73") (name "Net-(U2-C2P)") (class "Default")
      (node (ref "C20") (pin "2") (pinfunction "2_2") (pintype "passive"))
      (node (ref "U2") (pin "1") (pinfunction "C2P_1") (pintype "input"))
    )
    (net (code "74") (name "Net-(U2-IREF)") (class "Default")
      (node (ref "R7") (pin "2") (pinfunction "2_2") (pintype "passive"))
      (node (ref "U2") (pin "13") (pinfunction "IREF_13") (pintype "input"))
    )
    (net (code "75") (name "Net-(U2-VCC)") (class "Default")
      (node (ref "C23") (pin "2") (pinfunction "2_2") (pintype "passive"))
      (node (ref "U2") (pin "15") (pinfunction "VCC_15") (pintype "power_in"))
    )
    (net (code "76") (name "Net-(U2-VCOMH)") (class "Default")
      (node (ref "C22") (pin "2") (pinfunction "2_2") (pintype "passive"))
      (node (ref "U2") (pin "14") (pinfunction "VCOMH_14") (pintype "output"))
    )
    (net (code "77") (name "Net-(U5-UD+)") (class "Default")
      (node (ref "J2") (pin "A6") (pinfunction "D+_A6") (pintype "bidirectional"))
      (node (ref "J2") (pin "B6") (pinfunction "D+_B6") (pintype "bidirectional"))
      (node (ref "U5") (pin "5") (pinfunction "UD+_5") (pintype "bidirectional"))
    )
    (net (code "78") (name "Net-(U5-UD-)") (class "Default")
      (node (ref "J2") (pin "A7") (pinfunction "D-_A7") (pintype "bidirectional"))
      (node (ref "J2") (pin "B7") (pinfunction "D-_B7") (pintype "bidirectional"))
      (node (ref "U5") (pin "6") (pinfunction "UD-_6") (pintype "bidirectional"))
    )
    (net (code "79") (name "unconnected-(JP1-Pad7)") (class "Default")
      (node (ref "JP1") (pin "7") (pinfunction "7_7") (pintype "passive"))
    )
    (net (code "80") (name "unconnected-(JP1-Pad11)") (class "Default")
      (node (ref "JP1") (pin "11") (pinfunction "11_11") (pintype "passive"))
    )
    (net (code "81") (name "unconnected-(JP1-Pad12)") (class "Default")
      (node (ref "JP1") (pin "12") (pinfunction "12_12") (pintype "passive"))
    )
    (net (code "82") (name "unconnected-(JP1-Pad38)") (class "Default")
      (node (ref "JP1") (pin "38") (pinfunction "38_38") (pintype "passive"))
    )
    (net (code "83") (name "unconnected-(SD1-~{CARD}-Pad9)") (class "Default")
      (node (ref "SD1") (pin "9") (pinfunction "~{CARD}_9") (pintype "passive"))
    )
    (net (code "84") (name "unconnected-(U$1-FMINL-PadP$84)") (class "Default")
      (node (ref "U$1") (pin "P$84") (pinfunction "FMINL_P$84") (pintype "bidirectional"))
    )
    (net (code "85") (name "unconnected-(U$1-FMINR-PadP$85)") (class "Default")
      (node (ref "U$1") (pin "P$85") (pinfunction "FMINR_P$85") (pintype "bidirectional"))
    )
    (net (code "86") (name "unconnected-(U$1-HPCOM-PadP$3)") (class "Default")
      (node (ref "U$1") (pin "P$3") (pinfunction "HPCOM_P$3") (pintype "bidirectional"))
    )
    (net (code "87") (name "unconnected-(U$1-HPCOMFB-PadP$2)") (class "Default")
      (node (ref "U$1") (pin "P$2") (pinfunction "HPCOMFB_P$2") (pintype "bidirectional"))
    )
    (net (code "88") (name "unconnected-(U$1-HPL-PadP$1)") (class "Default")
      (node (ref "U$1") (pin "P$1") (pinfunction "HPL_P$1") (pintype "bidirectional"))
    )
    (net (code "89") (name "unconnected-(U$1-HPR-PadP$88)") (class "Default")
      (node (ref "U$1") (pin "P$88") (pinfunction "HPR_P$88") (pintype "bidirectional"))
    )
    (net (code "90") (name "unconnected-(U$1-HPVCC-PadP$4)") (class "Default")
      (node (ref "U$1") (pin "P$4") (pinfunction "HPVCC_P$4") (pintype "bidirectional"))
    )
    (net (code "91") (name "unconnected-(U$1-LINL-PadP$86)") (class "Default")
      (node (ref "U$1") (pin "P$86") (pinfunction "LINL_P$86") (pintype "bidirectional"))
    )
    (net (code "92") (name "unconnected-(U$1-LRADC0-PadP$79)") (class "Default")
      (node (ref "U$1") (pin "P$79") (pinfunction "LRADC0_P$79") (pintype "bidirectional"))
    )
    (net (code "93") (name "unconnected-(U$1-MICIN-PadP$87)") (class "Default")
      (node (ref "U$1") (pin "P$87") (pinfunction "MICIN_P$87") (pintype "bidirectional"))
    )
    (net (code "94") (name "unconnected-(U$1-PD0-PadP$6)") (class "Default")
      (node (ref "U$1") (pin "P$6") (pinfunction "PD0_P$6") (pintype "bidirectional"))
    )
    (net (code "95") (name "unconnected-(U$1-PD1-PadP$7)") (class "Default")
      (node (ref "U$1") (pin "P$7") (pinfunction "PD1_P$7") (pintype "bidirectional"))
    )
    (net (code "96") (name "unconnected-(U$1-PD2-PadP$8)") (class "Default")
      (node (ref "U$1") (pin "P$8") (pinfunction "PD2_P$8") (pintype "bidirectional"))
    )
    (net (code "97") (name "unconnected-(U$1-PD3-PadP$9)") (class "Default")
      (node (ref "U$1") (pin "P$9") (pinfunction "PD3_P$9") (pintype "bidirectional"))
    )
    (net (code "98") (name "unconnected-(U$1-PD4-PadP$10)") (class "Default")
      (node (ref "U$1") (pin "P$10") (pinfunction "PD4_P$10") (pintype "bidirectional"))
    )
    (net (code "99") (name "unconnected-(U$1-PD5-PadP$11)") (class "Default")
      (node (ref "U$1") (pin "P$11") (pinfunction "PD5_P$11") (pintype "bidirectional"))
    )
    (net (code "100") (name "unconnected-(U$1-PD6-PadP$12)") (class "Default")
      (node (ref "U$1") (pin "P$12") (pinfunction "PD6_P$12") (pintype "bidirectional"))
    )
    (net (code "101") (name "unconnected-(U$1-PD7-PadP$13)") (class "Default")
      (node (ref "U$1") (pin "P$13") (pinfunction "PD7_P$13") (pintype "bidirectional"))
    )
    (net (code "102") (name "unconnected-(U$1-PD8-PadP$14)") (class "Default")
      (node (ref "U$1") (pin "P$14") (pinfunction "PD8_P$14") (pintype "bidirectional"))
    )
    (net (code "103") (name "unconnected-(U$1-PD9-PadP$15)") (class "Default")
      (node (ref "U$1") (pin "P$15") (pinfunction "PD9_P$15") (pintype "bidirectional"))
    )
    (net (code "104") (name "unconnected-(U$1-PD10-PadP$16)") (class "Default")
      (node (ref "U$1") (pin "P$16") (pinfunction "PD10_P$16") (pintype "bidirectional"))
    )
    (net (code "105") (name "unconnected-(U$1-PD11-PadP$17)") (class "Default")
      (node (ref "U$1") (pin "P$17") (pinfunction "PD11_P$17") (pintype "bidirectional"))
    )
    (net (code "106") (name "unconnected-(U$1-PD12-PadP$18)") (class "Default")
      (node (ref "U$1") (pin "P$18") (pinfunction "PD12_P$18") (pintype "bidirectional"))
    )
    (net (code "107") (name "unconnected-(U$1-PD18-PadP$26)") (class "Default")
      (node (ref "U$1") (pin "P$26") (pinfunction "PD18_P$26") (pintype "bidirectional"))
    )
    (net (code "108") (name "unconnected-(U$1-PD19-PadP$27)") (class "Default")
      (node (ref "U$1") (pin "P$27") (pinfunction "PD19_P$27") (pintype "bidirectional"))
    )
    (net (code "109") (name "unconnected-(U$1-TV-VRN-PadP$75)") (class "Default")
      (node (ref "U$1") (pin "P$75") (pinfunction "TV-VRN_P$75") (pintype "bidirectional"))
    )
    (net (code "110") (name "unconnected-(U$1-TV-VRP-PadP$76)") (class "Default")
      (node (ref "U$1") (pin "P$76") (pinfunction "TV-VRP_P$76") (pintype "bidirectional"))
    )
    (net (code "111") (name "unconnected-(U$1-TVIN0-PadP$78)") (class "Default")
      (node (ref "U$1") (pin "P$78") (pinfunction "TVIN0_P$78") (pintype "bidirectional"))
    )
    (net (code "112") (name "unconnected-(U$1-TVIN1-PadP$77)") (class "Default")
      (node (ref "U$1") (pin "P$77") (pinfunction "TVIN1_P$77") (pintype "bidirectional"))
    )
    (net (code "113") (name "unconnected-(U$1-TVOUT-PadP$72)") (class "Default")
      (node (ref "U$1") (pin "P$72") (pinfunction "TVOUT_P$72") (pintype "bidirectional"))
    )
    (net (code "114") (name "unconnected-(U$1-VRA1-PadP$81)") (class "Default")
      (node (ref "U$1") (pin "P$81") (pinfunction "VRA1_P$81") (pintype "bidirectional"))
    )
    (net (code "115") (name "unconnected-(U$1-VRA2-PadP$83)") (class "Default")
      (node (ref "U$1") (pin "P$83") (pinfunction "VRA2_P$83") (pintype "bidirectional"))
    )
    (net (code "116") (name "unconnected-(U1A-PRTPWR-Pad12)") (class "Default")
      (node (ref "U1") (pin "12") (pinfunction "PRTPWR_12") (pintype "bidirectional"))
    )
    (net (code "117") (name "unconnected-(U1A-~{OCS}-Pad13)") (class "Default")
      (node (ref "U1") (pin "13") (pinfunction "~{OCS}_13") (pintype "bidirectional"))
    )
    (net (code "118") (name "unconnected-(U1B-PRTPWR-Pad16)") (class "Default")
      (node (ref "U1") (pin "16") (pinfunction "PRTPWR_16") (pintype "bidirectional"))
    )
    (net (code "119") (name "unconnected-(U1B-~{OCS}-Pad17)") (class "Default")
      (node (ref "U1") (pin "17") (pinfunction "~{OCS}_17") (pintype "bidirectional"))
    )
    (net (code "120") (name "unconnected-(U1C-PRTPWR-Pad18)") (class "Default")
      (node (ref "U1") (pin "18") (pinfunction "PRTPWR_18") (pintype "bidirectional"))
    )
    (net (code "121") (name "unconnected-(U1C-~{OCS}-Pad19)") (class "Default")
      (node (ref "U1") (pin "19") (pinfunction "~{OCS}_19") (pintype "bidirectional"))
    )
    (net (code "122") (name "unconnected-(U1D-PRTPWR-Pad20)") (class "Default")
      (node (ref "U1") (pin "20") (pinfunction "PRTPWR_20") (pintype "bidirectional"))
    )
    (net (code "123") (name "unconnected-(U1D-~{OCS}-Pad21)") (class "Default")
      (node (ref "U1") (pin "21") (pinfunction "~{OCS}_21") (pintype "bidirectional"))
    )
    (net (code "124") (name "unconnected-(U1E-TEST-Pad11)") (class "Default")
      (node (ref "U1") (pin "11") (pinfunction "TEST_11") (pintype "bidirectional"))
    )
    (net (code "125") (name "unconnected-(U5-R232-Pad15)") (class "Default")
      (node (ref "U5") (pin "15") (pinfunction "R232_15") (pintype "bidirectional"))
    )
    (net (code "126") (name "unconnected-(U5-~{CTS}-Pad9)") (class "Default")
      (node (ref "U5") (pin "9") (pinfunction "~{CTS}_9") (pintype "bidirectional"))
    )
    (net (code "127") (name "unconnected-(U5-~{DCD}-Pad12)") (class "Default")
      (node (ref "U5") (pin "12") (pinfunction "~{DCD}_12") (pintype "bidirectional"))
    )
    (net (code "128") (name "unconnected-(U5-~{DSR}-Pad10)") (class "Default")
      (node (ref "U5") (pin "10") (pinfunction "~{DSR}_10") (pintype "bidirectional"))
    )
    (net (code "129") (name "unconnected-(U5-~{DTR}-Pad13)") (class "Default")
      (node (ref "U5") (pin "13") (pinfunction "~{DTR}_13") (pintype "bidirectional"))
    )
    (net (code "130") (name "unconnected-(U5-~{RI}-Pad11)") (class "Default")
      (node (ref "U5") (pin "11") (pinfunction "~{RI}_11") (pintype "bidirectional"))
    )
    (net (code "131") (name "unconnected-(U5-~{RTS}-Pad14)") (class "Default")
      (node (ref "U5") (pin "14") (pinfunction "~{RTS}_14") (pintype "bidirectional"))
    )
  )
)
